# power.net
KiCad netlist of a schematic drawn in Altium Designer
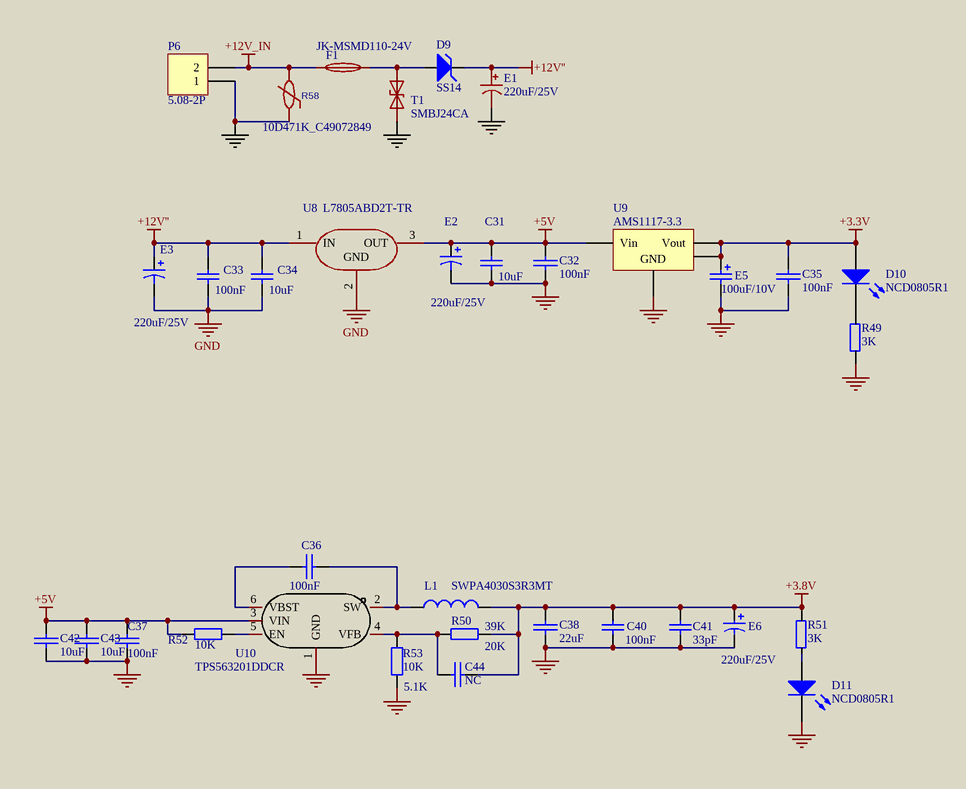
[diagram p0: power.SchDoc]

(export (version "E")
  (design (tool "Eeschema 10.0.6"))
  (components
    (comp (ref "C31")
      (value "10uF")
      (footprint "LC-0805_C")
      (description "Capacitor")
      (fields (field (name "PUBLISHER") "Altium Limited"))
      (libsource (lib "STM32F103RB(8)T6最小系统") (part "Cap"))
    )
    (comp (ref "C32")
      (value "100nF")
      (footprint "LC-0805_C")
      (description "Capacitor")
      (libsource (lib "*") (part "CAP"))
    )
    (comp (ref "C33")
      (value "100nF")
      (footprint "LC-0805_C")
      (description "Capacitor")
      (fields (field (name "PUBLISHER") "Altium Limited"))
      (libsource (lib "STM32F103RB(8)T6最小系统") (part "Cap"))
    )
    (comp (ref "C34")
      (value "10uF")
      (footprint "LC-0805_C")
      (description "Capacitor")
      (fields (field (name "PUBLISHER") "Altium Limited"))
      (libsource (lib "STM32F103RB(8)T6最小系统") (part "Cap"))
    )
    (comp (ref "C35")
      (value "100nF")
      (footprint "LC-0805_C")
      (description "Capacitor")
      (libsource (lib "*") (part "CAP"))
    )
    (comp (ref "C36")
      (value "100nF")
      (footprint "LC-0805_C")
      (description "Capacitor")
      (libsource (lib "*") (part "CAP"))
    )
    (comp (ref "C37")
      (value "100nF")
      (footprint "LC-0805_C")
      (description "Capacitor")
      (libsource (lib "*") (part "CAP"))
    )
    (comp (ref "C38")
      (value "22uF")
      (footprint "LC-1206_C")
      (description "Capacitor")
      (libsource (lib "*") (part "CAP"))
    )
    (comp (ref "C40")
      (value "100nF")
      (footprint "LC-0805_C")
      (description "Capacitor")
      (fields (field (name "PUBLISHER") "Altium Limited"))
      (libsource (lib "") (part "CAP_1"))
    )
    (comp (ref "C41")
      (value "33pF")
      (footprint "LC-0805_C")
      (description "Capacitor")
      (fields (field (name "PUBLISHER") "Altium Limited"))
      (libsource (lib "") (part "CAP_1"))
    )
    (comp (ref "C42")
      (value "10uF")
      (footprint "LC-1206_C")
      (description "Capacitor")
      (libsource (lib "*") (part "CAP"))
    )
    (comp (ref "C43")
      (value "10uF")
      (footprint "LC-1206_C")
      (description "Capacitor")
      (libsource (lib "*") (part "CAP"))
    )
    (comp (ref "C44")
      (value "NC")
      (footprint "LC-0805_C")
      (description "Capacitor")
      (libsource (lib "*") (part "CAP"))
    )
    (comp (ref "D9")
      (value "SS14")
      (footprint "LC-SMA(DO-214AC)_S5")
      (description "constant diode")
      (libsource (lib "*") (part "CONSTANT"))
    )
    (comp (ref "D10")
      (value "NCD0805R1")
      (footprint "LC-0805_LED_S1")
      (description "Typical BLUE SiC LED")
      (fields (field (name "PUBLISHER") "Altium Limited"))
      (libsource (lib "Miscellaneous Devices") (part "LED3"))
    )
    (comp (ref "D11")
      (value "NCD0805R1")
      (footprint "LC-0805_LED_S1")
      (description "Typical BLUE SiC LED")
      (fields (field (name "PUBLISHER") "Altium Limited"))
      (libsource (lib "Miscellaneous Devices") (part "LED3"))
    )
    (comp (ref "E1")
      (value "220uF/25V")
      (footprint "CAP-TH_BD6.3-P2.50")
      (fields
        (field (name "MANUFACTURER") "rubycon(红宝石)")
        (field (name "MANUFACTURER PART") "35YXJ470M10x16")
        (field (name "TOLERANCE") "±20%")
      )
      (libsource (lib "altium-import") (part "root_3_35YXJ470M10x16_"))
    )
    (comp (ref "E2")
      (value "220uF/25V")
      (footprint "CAP-TH_BD6.3-P2.50")
      (description "Polarized Capacitor (Radial)")
      (fields (field (name "PUBLISHER") "Altium Limited"))
      (libsource (lib "STM32F103RB(8)T6最小系统") (part "Cap Pol1"))
    )
    (comp (ref "E3")
      (value "220uF/25V")
      (footprint "CAP-TH_BD6.3-P2.50")
      (description "Polarized Capacitor (Radial)")
      (fields (field (name "PUBLISHER") "Altium Limited"))
      (libsource (lib "STM32F103RB(8)T6最小系统") (part "Cap Pol1"))
    )
    (comp (ref "E5")
      (value "100uF/10V")
      (footprint "3528_B")
      (description "Polarized Capacitor (Radial)")
      (fields (field (name "PUBLISHER") "Altium Limited"))
      (libsource (lib "*") (part "Cap Pol1"))
    )
    (comp (ref "E6")
      (value "220uF/25V")
      (footprint "CAP-TH_BD6.3-P2.50")
      (description "Bi-Polar Capacitor")
      (libsource (lib "*") (part "CAP2"))
    )
    (comp (ref "F1")
      (value "JK-MSMD110-24V")
      (footprint "F1812")
      (fields (field (name "MANUFACTURER") "JK(金科)"))
      (libsource (lib "altium-import") (part "root_0_JK-MSMD110-24V_"))
    )
    (comp (ref "L1")
      (value "SWPA4030S3R3MT")
      (footprint "LC-4.0*4.0")
      (description "Inductor")
      (fields (field (name "PUBLISHER") "Altium Limited"))
      (libsource (lib "Miscellaneous Devices") (part "Inductor"))
    )
    (comp (ref "P6")
      (value "5.08-2P")
      (footprint "MKDSN_2RMI")
      (description "Header, 2-Pin")
      (fields (field (name "PUBLISHER") "Altium Limited"))
      (libsource (lib "Miscellaneous Connectors") (part "Header 2"))
    )
    (comp (ref "R49") (value "3K") (footprint "LC-0805_R") (libsource (lib "ATK-SIM900A") (part "R")))
    (comp (ref "R50")
      (value "39K")
      (footprint "LC-0805_R")
      (description "Resistor")
      (fields (field (name "PUBLISHER") "Altium Limited"))
      (libsource (lib "") (part "Res2_2"))
    )
    (comp (ref "R51") (value "3K") (footprint "LC-0805_R") (libsource (lib "ATK-SIM900A") (part "R")))
    (comp (ref "R52")
      (value "10K")
      (footprint "LC-0805_R")
      (description "Resistor")
      (fields (field (name "PUBLISHER") "Altium Limited"))
      (libsource (lib "Miscellaneous Devices") (part "Res2"))
    )
    (comp (ref "R53")
      (value "10K")
      (footprint "LC-0805_R")
      (description "Resistor")
      (fields (field (name "PUBLISHER") "Altium Limited"))
      (libsource (lib "") (part "Res2_1"))
    )
    (comp (ref "R58")
      (value "10D471K_C49072849")
      (footprint "RES-TH_L11.0-W6.0-P7.50")
      (libsource (lib "altium-import") (part "root_1_14D471K_C49069733_"))
    )
    (comp (ref "T1")
      (value "SMBJ24CA")
      (footprint "SMB_L4.6-W3.6-LS5.3-BI")
      (fields (field (name "MANUFACTURER") "Brightking(君耀电子)"))
      (libsource (lib "altium-import") (part "root_3_SMBJ24CA_C78416_"))
    )
    (comp (ref "U8")
      (value "L7805ABD2T-TR")
      (footprint "LC-TO-263-2")
      (fields (field (name "MANUFACTURER") "ST(意法半导体)") (field (name "MANUFACTURER PART") "L7805CV-DG"))
      (libsource (lib "altium-import") (part "root_0_L7805CV-DG_"))
    )
    (comp (ref "U9")
      (value "AMS1117-3.3")
      (footprint "LC-SOT-223")
      (description "Voltage Regulator")
      (fields (field (name "PUBLISHER") "Altium Limited"))
      (libsource (lib "EPS") (part "Volt Reg"))
    )
    (comp (ref "U10")
      (value "TPS563201DDCR")
      (footprint "LC-SOT-23-6")
      (fields (field (name "MANUFACTURER") "TI(德州仪器)"))
      (libsource (lib "altium-import") (part "root_0_mirrored_TPS563201DDCR_"))
    )
  )
  (nets
    (net (code "1") (name "+3.3V") (class "Default")
      (node (ref "C35") (pin "1") (pinfunction "1_1") (pintype "passive"))
      (node (ref "D10") (pin "1") (pinfunction "A_1") (pintype "passive"))
      (node (ref "E5") (pin "1") (pinfunction "1_1") (pintype "passive"))
      (node (ref "U9") (pin "3") (pinfunction "Vout_3") (pintype "passive"))
      (node (ref "U9") (pin "4") (pinfunction "Vout_4") (pintype "passive"))
    )
    (net (code "2") (name "+3.8V") (class "Default")
      (node (ref "C38") (pin "1") (pinfunction "1_1") (pintype "passive"))
      (node (ref "C40") (pin "1") (pinfunction "1_1") (pintype "passive"))
      (node (ref "C41") (pin "1") (pinfunction "1_1") (pintype "passive"))
      (node (ref "C44") (pin "1") (pinfunction "1_1") (pintype "passive"))
      (node (ref "E6") (pin "1") (pinfunction "1_1") (pintype "passive"))
      (node (ref "L1") (pin "2") (pinfunction "2_2") (pintype "passive"))
      (node (ref "R50") (pin "1") (pinfunction "1_1") (pintype "passive"))
      (node (ref "R51") (pin "1") (pintype "passive"))
    )
    (net (code "3") (name "+5V") (class "Default")
      (node (ref "C31") (pin "1") (pinfunction "1_1") (pintype "passive"))
      (node (ref "C32") (pin "1") (pinfunction "1_1") (pintype "passive"))
      (node (ref "C37") (pin "2") (pinfunction "2_2") (pintype "passive"))
      (node (ref "C42") (pin "1") (pinfunction "1_1") (pintype "passive"))
      (node (ref "C43") (pin "1") (pinfunction "1_1") (pintype "passive"))
      (node (ref "E2") (pin "1") (pinfunction "1_1") (pintype "passive"))
      (node (ref "R52") (pin "1") (pinfunction "1_1") (pintype "passive"))
      (node (ref "U10") (pin "3") (pinfunction "VIN_3") (pintype "passive"))
      (node (ref "U8") (pin "3") (pinfunction "OUT_3") (pintype "passive"))
      (node (ref "U9") (pin "1") (pinfunction "Vin_1") (pintype "passive"))
    )
    (net (code "4") (name "+12V''") (class "Default")
      (node (ref "C33") (pin "1") (pinfunction "1_1") (pintype "passive"))
      (node (ref "C34") (pin "1") (pinfunction "1_1") (pintype "passive"))
      (node (ref "D9") (pin "2") (pinfunction "K_2") (pintype "passive"))
      (node (ref "E1") (pin "1") (pinfunction "1_1") (pintype "passive"))
      (node (ref "E3") (pin "1") (pinfunction "1_1") (pintype "passive"))
      (node (ref "U8") (pin "1") (pinfunction "IN_1") (pintype "passive"))
    )
    (net (code "5") (name "+12V_IN") (class "Default")
      (node (ref "F1") (pin "1") (pinfunction "1_1") (pintype "passive"))
      (node (ref "P6") (pin "2") (pinfunction "2_2") (pintype "passive"))
      (node (ref "R58") (pin "2") (pinfunction "2_2") (pintype "passive"))
    )
    (net (code "6") (name "GND") (class "Default")
      (node (ref "C31") (pin "2") (pinfunction "2_2") (pintype "passive"))
      (node (ref "C32") (pin "2") (pinfunction "2_2") (pintype "passive"))
      (node (ref "C33") (pin "2") (pinfunction "2_2") (pintype "passive"))
      (node (ref "C34") (pin "2") (pinfunction "2_2") (pintype "passive"))
      (node (ref "C35") (pin "2") (pinfunction "2_2") (pintype "passive"))
      (node (ref "C37") (pin "1") (pinfunction "1_1") (pintype "passive"))
      (node (ref "C38") (pin "2") (pinfunction "2_2") (pintype "passive"))
      (node (ref "C40") (pin "2") (pinfunction "2_2") (pintype "passive"))
      (node (ref "C41") (pin "2") (pinfunction "2_2") (pintype "passive"))
      (node (ref "C42") (pin "2") (pinfunction "2_2") (pintype "passive"))
      (node (ref "C43") (pin "2") (pinfunction "2_2") (pintype "passive"))
      (node (ref "D11") (pin "2") (pinfunction "K_2") (pintype "passive"))
      (node (ref "E1") (pin "2") (pinfunction "2_2") (pintype "passive"))
      (node (ref "E2") (pin "2") (pinfunction "2_2") (pintype "passive"))
      (node (ref "E3") (pin "2") (pinfunction "2_2") (pintype "passive"))
      (node (ref "E5") (pin "2") (pinfunction "2_2") (pintype "passive"))
      (node (ref "E6") (pin "2") (pinfunction "2_2") (pintype "passive"))
      (node (ref "P6") (pin "1") (pinfunction "1_1") (pintype "passive"))
      (node (ref "R49") (pin "2") (pintype "passive"))
      (node (ref "R53") (pin "1") (pinfunction "1_1") (pintype "passive"))
      (node (ref "R58") (pin "1") (pinfunction "1_1") (pintype "passive"))
      (node (ref "T1") (pin "1") (pinfunction "K_1") (pintype "passive"))
      (node (ref "U10") (pin "1") (pinfunction "GND_1") (pintype "passive"))
      (node (ref "U8") (pin "2") (pinfunction "GND_2") (pintype "passive"))
      (node (ref "U9") (pin "2") (pinfunction "GND_2") (pintype "passive"))
    )
    (net (code "7") (name "Net-(D9-A)") (class "Default")
      (node (ref "D9") (pin "1") (pinfunction "A_1") (pintype "passive"))
      (node (ref "F1") (pin "2") (pinfunction "2_2") (pintype "passive"))
      (node (ref "T1") (pin "2") (pinfunction "A_2") (pintype "passive"))
    )
    (net (code "8") (name "Net-(D10-K)") (class "Default")
      (node (ref "D10") (pin "2") (pinfunction "K_2") (pintype "passive"))
      (node (ref "R49") (pin "1") (pintype "passive"))
    )
    (net (code "9") (name "Net-(D11-A)") (class "Default")
      (node (ref "D11") (pin "1") (pinfunction "A_1") (pintype "passive"))
      (node (ref "R51") (pin "2") (pintype "passive"))
    )
    (net (code "10") (name "Net-(U10-EN)") (class "Default")
      (node (ref "R52") (pin "2") (pinfunction "2_2") (pintype "passive"))
      (node (ref "U10") (pin "5") (pinfunction "EN_5") (pintype "passive"))
    )
    (net (code "11") (name "Net-(U10-SW)") (class "Default")
      (node (ref "C36") (pin "2") (pinfunction "2_2") (pintype "passive"))
      (node (ref "L1") (pin "1") (pinfunction "1_1") (pintype "passive"))
      (node (ref "U10") (pin "2") (pinfunction "SW_2") (pintype "passive"))
    )
    (net (code "12") (name "Net-(U10-VBST)") (class "Default")
      (node (ref "C36") (pin "1") (pinfunction "1_1") (pintype "passive"))
      (node (ref "U10") (pin "6") (pinfunction "VBST_6") (pintype "passive"))
    )
    (net (code "13") (name "Net-(U10-VFB)") (class "Default")
      (node (ref "C44") (pin "2") (pinfunction "2_2") (pintype "passive"))
      (node (ref "R50") (pin "2") (pinfunction "2_2") (pintype "passive"))
      (node (ref "R53") (pin "2") (pinfunction "2_2") (pintype "passive"))
      (node (ref "U10") (pin "4") (pinfunction "VFB_4") (pintype "passive"))
    )
  )
)
